# Breakout.net
KiCad netlist of a schematic drawn in EAGLE
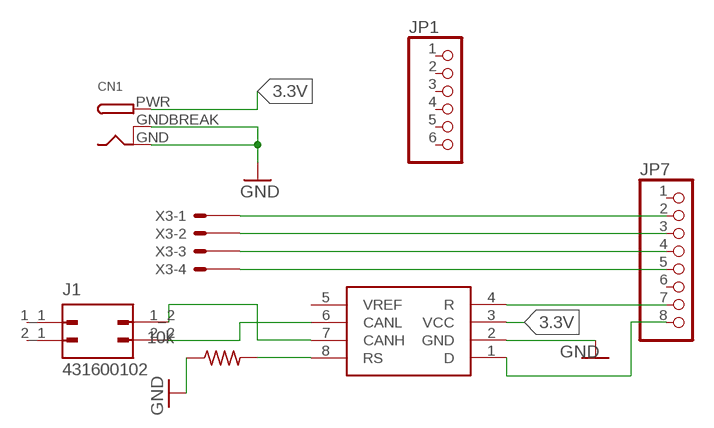
[diagram p0: schematic, sheet 1]

(export (version "E")
  (design (tool "Eeschema 10.0.6"))
  (components
    (comp (ref "CN1")
      (value "DCBARRELPTH")
      (footprint "eagle-import:DCJACK_2MM_PTH")
      (libsource (lib "eagle-import") (part "DCBARRELPTH"))
    )
    (comp (ref "IC1")
      (value "SN65HVD231D")
      (footprint "eagle-import:SOIC127P600X175-8N")
      (fields (field (name "MOUSER_PART_NUMBER") "595-SN65HVD231D"))
      (libsource (lib "eagle-import") (part "SN65HVD231D"))
    )
    (comp (ref "J1")
      (value "431600102")
      (footprint "eagle-import:MOLEX_431600102")
      (fields (field (name "MF") "Molex") (field (name "MP") "43160-0102"))
      (libsource (lib "eagle-import") (part "431600102"))
    )
    (comp (ref "JP1")
      (value "PINHD-1X6")
      (footprint "eagle-import:1X06")
      (libsource (lib "eagle-import") (part "PINHD-1X6"))
    )
    (comp (ref "JP7")
      (value "PINHD-1X8")
      (footprint "eagle-import:1X08")
      (libsource (lib "eagle-import") (part "PINHD-1X8"))
    )
    (comp (ref "R5")
      (value "10k")
      (footprint "eagle-import:0204_5")
      (libsource (lib "eagle-import") (part "R-US_0204/5"))
    )
    (comp (ref "X3")
      (value "43160-5304")
      (footprint "eagle-import:43160-XX04")
      (fields (field (name "MF") "MOLEX"))
      (libsource (lib "eagle-import") (part "43160-0453"))
    )
  )
  (nets
    (net (code "1") (name "3.3V") (class "Default")
      (node (ref "CN1") (pin "PWR") (pinfunction "PWR_PWR") (pintype "power_in"))
      (node (ref "IC1") (pin "3") (pinfunction "VCC_3") (pintype "bidirectional"))
    )
    (net (code "2") (name "GND") (class "Default")
      (node (ref "CN1") (pin "GND") (pinfunction "GND_GND") (pintype "power_in"))
      (node (ref "CN1") (pin "GNDBREAK") (pinfunction "GNDBREAK_GNDBREAK") (pintype "power_in"))
      (node (ref "IC1") (pin "2") (pinfunction "GND_2") (pintype "bidirectional"))
      (node (ref "R5") (pin "1") (pinfunction "1_1") (pintype "passive"))
    )
    (net (code "3") (name "Net-(IC1-CANH)") (class "Default")
      (node (ref "IC1") (pin "7") (pinfunction "CANH_7") (pintype "bidirectional"))
      (node (ref "J1") (pin "1_2") (pinfunction "1_2_1_2") (pintype "passive"))
    )
    (net (code "4") (name "Net-(IC1-CANL)") (class "Default")
      (node (ref "IC1") (pin "6") (pinfunction "CANL_6") (pintype "bidirectional"))
      (node (ref "J1") (pin "2_2") (pinfunction "2_2_2_2") (pintype "passive"))
    )
    (net (code "5") (name "Net-(IC1-D)") (class "Default")
      (node (ref "IC1") (pin "1") (pinfunction "D_1") (pintype "bidirectional"))
      (node (ref "JP7") (pin "8") (pinfunction "8_8") (pintype "passive"))
    )
    (net (code "6") (name "Net-(IC1-R)") (class "Default")
      (node (ref "IC1") (pin "4") (pinfunction "R_4") (pintype "bidirectional"))
      (node (ref "JP7") (pin "7") (pinfunction "7_7") (pintype "passive"))
    )
    (net (code "7") (name "Net-(IC1-RS)") (class "Default")
      (node (ref "IC1") (pin "8") (pinfunction "RS_8") (pintype "bidirectional"))
      (node (ref "R5") (pin "2") (pinfunction "2_2") (pintype "passive"))
    )
    (net (code "8") (name "Net-(JP7-Pad2)") (class "Default")
      (node (ref "JP7") (pin "2") (pinfunction "2_2") (pintype "passive"))
      (node (ref "X3") (pin "1@1") (pinfunction "S_1@1") (pintype "passive"))
    )
    (net (code "9") (name "Net-(JP7-Pad3)") (class "Default")
      (node (ref "JP7") (pin "3") (pinfunction "3_3") (pintype "passive"))
      (node (ref "X3") (pin "2@1") (pinfunction "S_2@1") (pintype "passive"))
    )
    (net (code "10") (name "Net-(JP7-Pad4)") (class "Default")
      (node (ref "JP7") (pin "4") (pinfunction "4_4") (pintype "passive"))
      (node (ref "X3") (pin "3@1") (pinfunction "S_3@1") (pintype "passive"))
    )
    (net (code "11") (name "Net-(JP7-Pad5)") (class "Default")
      (node (ref "JP7") (pin "5") (pinfunction "5_5") (pintype "passive"))
      (node (ref "X3") (pin "4@1") (pinfunction "S_4@1") (pintype "passive"))
    )
    (net (code "12") (name "unconnected-(IC1-VREF-Pad5)") (class "Default")
      (node (ref "IC1") (pin "5") (pinfunction "VREF_5") (pintype "bidirectional"))
    )
    (net (code "13") (name "unconnected-(J1-Pad1_1)") (class "Default")
      (node (ref "J1") (pin "1_1") (pinfunction "1_1_1_1") (pintype "passive"))
    )
    (net (code "14") (name "unconnected-(J1-Pad2_1)") (class "Default")
      (node (ref "J1") (pin "2_1") (pinfunction "2_1_2_1") (pintype "passive"))
    )
    (net (code "15") (name "unconnected-(JP1-Pad1)") (class "Default")
      (node (ref "JP1") (pin "1") (pinfunction "1_1") (pintype "passive"))
    )
    (net (code "16") (name "unconnected-(JP1-Pad2)") (class "Default")
      (node (ref "JP1") (pin "2") (pinfunction "2_2") (pintype "passive"))
    )
    (net (code "17") (name "unconnected-(JP1-Pad3)") (class "Default")
      (node (ref "JP1") (pin "3") (pinfunction "3_3") (pintype "passive"))
    )
    (net (code "18") (name "unconnected-(JP1-Pad4)") (class "Default")
      (node (ref "JP1") (pin "4") (pinfunction "4_4") (pintype "passive"))
    )
    (net (code "19") (name "unconnected-(JP1-Pad5)") (class "Default")
      (node (ref "JP1") (pin "5") (pinfunction "5_5") (pintype "passive"))
    )
    (net (code "20") (name "unconnected-(JP1-Pad6)") (class "Default")
      (node (ref "JP1") (pin "6") (pinfunction "6_6") (pintype "passive"))
    )
    (net (code "21") (name "unconnected-(JP7-Pad1)") (class "Default")
      (node (ref "JP7") (pin "1") (pinfunction "1_1") (pintype "passive"))
    )
    (net (code "22") (name "unconnected-(JP7-Pad6)") (class "Default")
      (node (ref "JP7") (pin "6") (pinfunction "6_6") (pintype "passive"))
    )
    (net (code "23") (name "unconnected-(X3A-S-Pad1@2)") (class "Default")
      (node (ref "X3") (pin "1@2") (pinfunction "S_1@2") (pintype "passive"))
    )
    (net (code "24") (name "unconnected-(X3B-S-Pad2@2)") (class "Default")
      (node (ref "X3") (pin "2@2") (pinfunction "S_2@2") (pintype "passive"))
    )
    (net (code "25") (name "unconnected-(X3C-S-Pad3@2)") (class "Default")
      (node (ref "X3") (pin "3@2") (pinfunction "S_3@2") (pintype "passive"))
    )
    (net (code "26") (name "unconnected-(X3D-S-Pad4@2)") (class "Default")
      (node (ref "X3") (pin "4@2") (pinfunction "S_4@2") (pintype "passive"))
    )
  )
)
